# ST14_POWER.net
KiCad netlist of a schematic drawn in Altium Designer
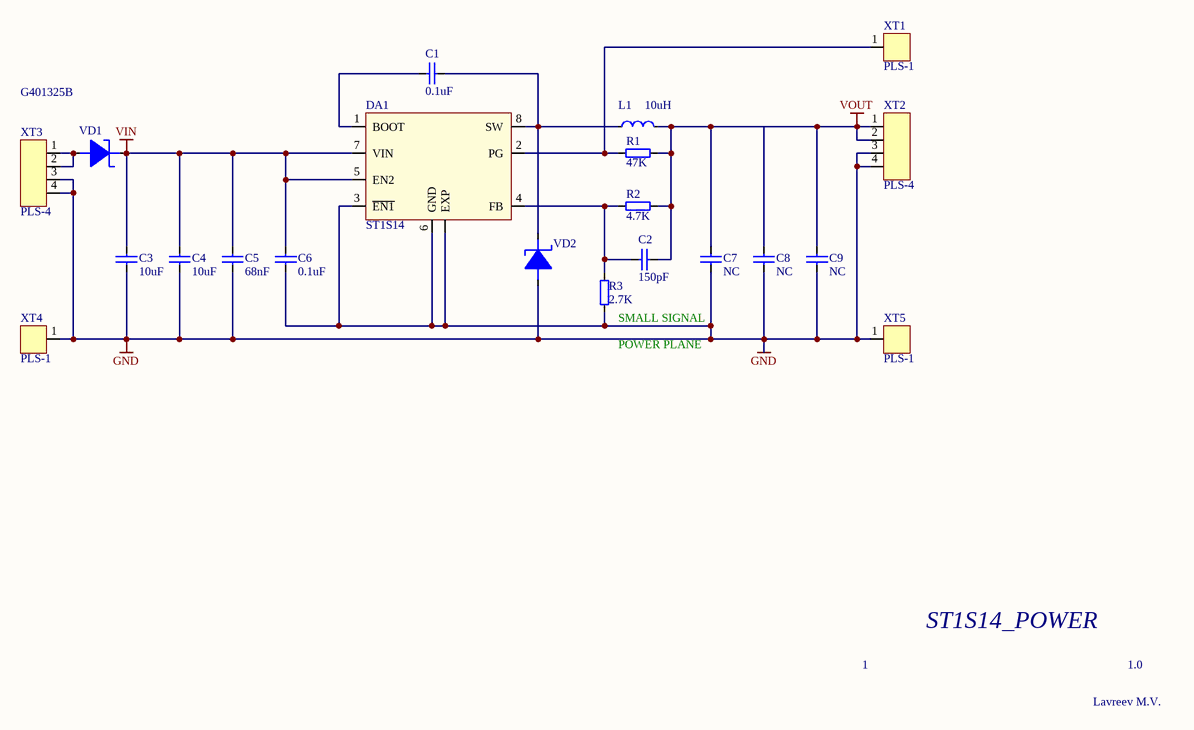
[diagram p0: ST14_POWER.SchDoc]

(export (version "E")
  (design (tool "Eeschema 10.0.6"))
  (components
    (comp (ref "C1")
      (value "0.1uF")
      (footprint "C0805")
      (description "Capacitor")
      (libsource (lib "C") (part "C"))
    )
    (comp (ref "C2")
      (value "150pF")
      (footprint "C0805")
      (description "Capacitor")
      (libsource (lib "C") (part "C"))
    )
    (comp (ref "C3")
      (value "10uF")
      (footprint "C1210")
      (description "Capacitor")
      (libsource (lib "C") (part "C"))
    )
    (comp (ref "C4")
      (value "10uF")
      (footprint "C1210")
      (description "Capacitor")
      (libsource (lib "C") (part "C"))
    )
    (comp (ref "C5")
      (value "68nF")
      (footprint "C0805")
      (description "Capacitor")
      (libsource (lib "C") (part "C"))
    )
    (comp (ref "C6")
      (value "0.1uF")
      (footprint "C0805")
      (description "Capacitor")
      (libsource (lib "C") (part "C"))
    )
    (comp (ref "C7")
      (value "NC")
      (footprint "C1210")
      (description "Capacitor")
      (libsource (lib "C") (part "C"))
    )
    (comp (ref "C8")
      (value "NC")
      (footprint "C0805")
      (description "Capacitor")
      (libsource (lib "C") (part "C"))
    )
    (comp (ref "C9")
      (value "NC")
      (footprint "C1210")
      (description "Capacitor")
      (libsource (lib "C") (part "C"))
    )
    (comp (ref "DA1")
      (value "ST1S14")
      (footprint "SO-8EPAD")
      (description "Up to 3 A step-down switching regulator")
      (libsource (lib "IC - Power") (part "ST1S14"))
    )
    (comp (ref "L1")
      (value "10uH")
      (footprint "MSS7341")
      (description "Inductor")
      (fields (field (name "PUBLISHER") "Altium Limited"))
      (libsource (lib "L") (part "L"))
    )
    (comp (ref "R1")
      (value "47K")
      (footprint "R0805")
      (description "Resistor")
      (libsource (lib "R") (part "R"))
    )
    (comp (ref "R2")
      (value "4.7K")
      (footprint "R0805")
      (description "Resistor")
      (libsource (lib "R") (part "R"))
    )
    (comp (ref "R3")
      (value "2.7K")
      (footprint "R0805")
      (description "Resistor")
      (libsource (lib "") (part "R_1"))
    )
    (comp (ref "VD1")
      (value "1N5819")
      (footprint "Diode SMB")
      (description "Diode")
      (libsource (lib "VD") (part "Diode Shottky"))
    )
    (comp (ref "VD2")
      (value "1N5819")
      (footprint "Diode SMB")
      (description "Diode")
      (libsource (lib "VD") (part "Diode Shottky"))
    )
    (comp (ref "XT1")
      (value "PLS-1")
      (footprint "PLS-1_1")
      (description "Pin Header Pitch 2.54mm 1 Pin")
      (libsource (lib "Connectors - Header") (part "PLS-1"))
    )
    (comp (ref "XT2")
      (value "PLS-4")
      (footprint "PLS-4_1")
      (description "Pin Header Pitch 2.54mm 4pins")
      (libsource (lib "") (part "PLS-4_1"))
    )
    (comp (ref "XT3")
      (value "PLS-4")
      (footprint "PLS-4_1")
      (description "Pin Header Pitch 2.54mm 4pins")
      (libsource (lib "Connectors - Header") (part "PLS-4"))
    )
    (comp (ref "XT4")
      (value "PLS-1")
      (footprint "PLS-1_1")
      (description "Pin Header Pitch 2.54mm 1 Pin")
      (libsource (lib "") (part "PLS-1_1"))
    )
    (comp (ref "XT5")
      (value "PLS-1")
      (footprint "PLS-1_1")
      (description "Pin Header Pitch 2.54mm 1 Pin")
      (libsource (lib "Connectors - Header") (part "PLS-1"))
    )
  )
  (nets
    (net (code "1") (name "GND") (class "Default")
      (node (ref "C3") (pin "1") (pinfunction "1_1") (pintype "passive"))
      (node (ref "C4") (pin "1") (pinfunction "1_1") (pintype "passive"))
      (node (ref "C5") (pin "1") (pinfunction "1_1") (pintype "passive"))
      (node (ref "C6") (pin "1") (pinfunction "1_1") (pintype "passive"))
      (node (ref "C7") (pin "1") (pinfunction "1_1") (pintype "passive"))
      (node (ref "C8") (pin "1") (pinfunction "1_1") (pintype "passive"))
      (node (ref "C9") (pin "1") (pinfunction "1_1") (pintype "passive"))
      (node (ref "DA1") (pin "0") (pinfunction "EXP_0") (pintype "passive"))
      (node (ref "DA1") (pin "3") (pinfunction "~{EN1}_3") (pintype "passive"))
      (node (ref "DA1") (pin "6") (pinfunction "GND_6") (pintype "passive"))
      (node (ref "R3") (pin "1") (pinfunction "1_1") (pintype "passive"))
      (node (ref "VD2") (pin "1") (pinfunction "A_1") (pintype "passive"))
      (node (ref "XT2") (pin "3") (pinfunction "3_3") (pintype "passive"))
      (node (ref "XT2") (pin "4") (pinfunction "4_4") (pintype "passive"))
      (node (ref "XT3") (pin "3") (pinfunction "3_3") (pintype "passive"))
      (node (ref "XT3") (pin "4") (pinfunction "4_4") (pintype "passive"))
      (node (ref "XT4") (pin "1") (pinfunction "1_1") (pintype "passive"))
      (node (ref "XT5") (pin "1") (pinfunction "1_1") (pintype "passive"))
    )
    (net (code "2") (name "Net-(DA1-BOOT)") (class "Default")
      (node (ref "C1") (pin "1") (pinfunction "1_1") (pintype "passive"))
      (node (ref "DA1") (pin "1") (pinfunction "BOOT_1") (pintype "passive"))
    )
    (net (code "3") (name "Net-(DA1-FB)") (class "Default")
      (node (ref "C2") (pin "1") (pinfunction "1_1") (pintype "passive"))
      (node (ref "DA1") (pin "4") (pinfunction "FB_4") (pintype "passive"))
      (node (ref "R2") (pin "1") (pinfunction "1_1") (pintype "passive"))
      (node (ref "R3") (pin "2") (pinfunction "2_2") (pintype "passive"))
    )
    (net (code "4") (name "Net-(DA1-PG)") (class "Default")
      (node (ref "DA1") (pin "2") (pinfunction "PG_2") (pintype "passive"))
      (node (ref "R1") (pin "1") (pinfunction "1_1") (pintype "passive"))
      (node (ref "XT1") (pin "1") (pinfunction "1_1") (pintype "passive"))
    )
    (net (code "5") (name "Net-(DA1-SW)") (class "Default")
      (node (ref "C1") (pin "2") (pinfunction "2_2") (pintype "passive"))
      (node (ref "DA1") (pin "8") (pinfunction "SW_8") (pintype "passive"))
      (node (ref "L1") (pin "2") (pinfunction "2_2") (pintype "passive"))
      (node (ref "VD2") (pin "2") (pinfunction "C_2") (pintype "passive"))
    )
    (net (code "6") (name "Net-(VD1-A)") (class "Default")
      (node (ref "VD1") (pin "1") (pinfunction "A_1") (pintype "passive"))
      (node (ref "XT3") (pin "1") (pinfunction "1_1") (pintype "passive"))
      (node (ref "XT3") (pin "2") (pinfunction "2_2") (pintype "passive"))
    )
    (net (code "7") (name "VIN") (class "Default")
      (node (ref "C3") (pin "2") (pinfunction "2_2") (pintype "passive"))
      (node (ref "C4") (pin "2") (pinfunction "2_2") (pintype "passive"))
      (node (ref "C5") (pin "2") (pinfunction "2_2") (pintype "passive"))
      (node (ref "C6") (pin "2") (pinfunction "2_2") (pintype "passive"))
      (node (ref "DA1") (pin "5") (pinfunction "EN2_5") (pintype "passive"))
      (node (ref "DA1") (pin "7") (pinfunction "VIN_7") (pintype "passive"))
      (node (ref "VD1") (pin "2") (pinfunction "C_2") (pintype "passive"))
    )
    (net (code "8") (name "VOUT") (class "Default")
      (node (ref "C2") (pin "2") (pinfunction "2_2") (pintype "passive"))
      (node (ref "C7") (pin "2") (pinfunction "2_2") (pintype "passive"))
      (node (ref "C8") (pin "2") (pinfunction "2_2") (pintype "passive"))
      (node (ref "C9") (pin "2") (pinfunction "2_2") (pintype "passive"))
      (node (ref "L1") (pin "1") (pinfunction "1_1") (pintype "passive"))
      (node (ref "R1") (pin "2") (pinfunction "2_2") (pintype "passive"))
      (node (ref "R2") (pin "2") (pinfunction "2_2") (pintype "passive"))
      (node (ref "XT2") (pin "1") (pinfunction "1_1") (pintype "passive"))
      (node (ref "XT2") (pin "2") (pinfunction "2_2") (pintype "passive"))
    )
  )
)
